# DRV.net
KiCad netlist of a schematic drawn in Altium Designer
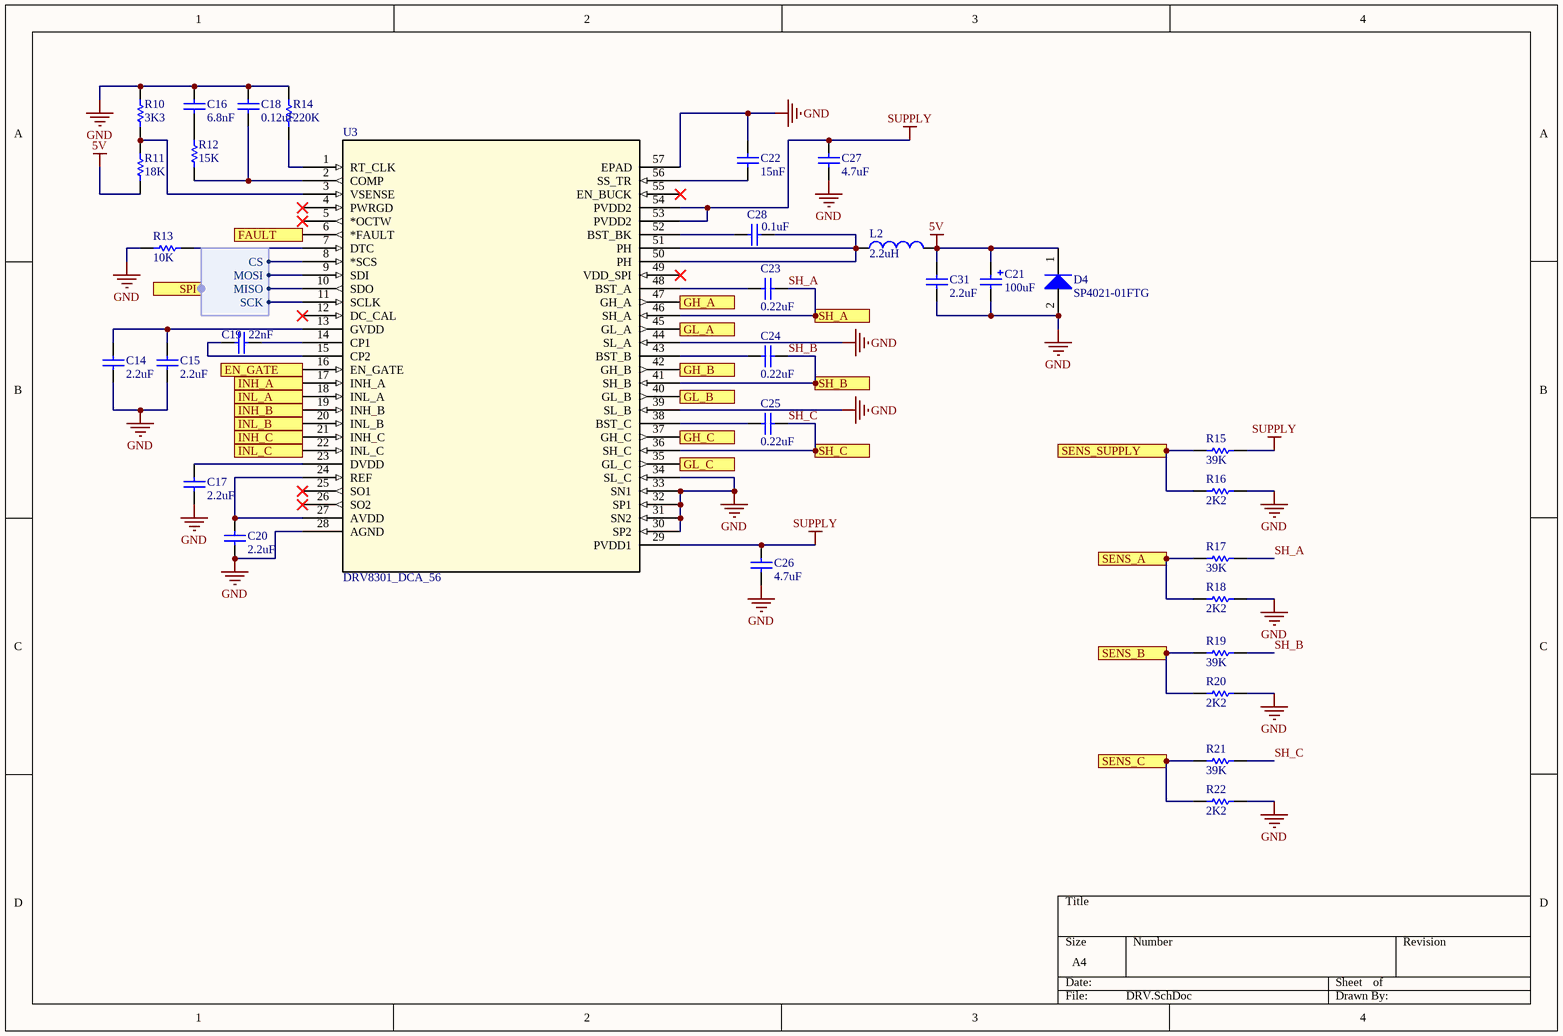
[diagram p0: DRV.SchDoc]

(export (version "E")
  (design (tool "Eeschema 10.0.6"))
  (components
    (comp (ref "C14")
      (value "2.2uF")
      (footprint "C0603[1608X92]")
      (description "2.2uF 25V 10% 0603 (1608 Metric)")
      (fields (field (name "PARTNUMBER") "GRM188R61E225KA12D") (field (name "MANUFACTURER") "Murata"))
      (libsource (lib "Capacitors") (part "CAP_2.2uF_25V_0603_10%"))
    )
    (comp (ref "C15")
      (value "2.2uF")
      (footprint "C0603[1608X92]")
      (description "2.2uF 25V 10% 0603 (1608 Metric)")
      (fields (field (name "PARTNUMBER") "GRM188R61E225KA12D") (field (name "MANUFACTURER") "Murata"))
      (libsource (lib "Capacitors") (part "CAP_2.2uF_25V_0603_10%"))
    )
    (comp (ref "C16")
      (value "6.8nF")
      (footprint "C0603[1608X92]")
      (description "6.8nF 50V 5% 0603 (1608 Metric)")
      (fields (field (name "PARTNUMBER") "GRM1885C1H682JA01D") (field (name "MANUFACTURER") "Murata"))
      (libsource (lib "Capacitors") (part "CAP_6.8nF_50V_0603_5%"))
    )
    (comp (ref "C17")
      (value "2.2uF")
      (footprint "C0603[1608X92]")
      (description "2.2uF 25V 10% 0603 (1608 Metric)")
      (fields (field (name "PARTNUMBER") "GRM188R61E225KA12D") (field (name "MANUFACTURER") "Murata"))
      (libsource (lib "Capacitors") (part "CAP_2.2uF_25V_0603_10%"))
    )
    (comp (ref "C18")
      (value "0.12uF")
      (footprint "C0603[1608X92]")
      (description "0.12uF 10V 10% 0603 (1608 Metric)")
      (fields (field (name "PARTNUMBER") "GRM188R71A124KA01D") (field (name "MANUFACTURER") "Murata"))
      (libsource (lib "Capacitors") (part "CAP_0.12uF_10V_0603_10%"))
    )
    (comp (ref "C19")
      (value "22nF")
      (footprint "C0603[1608X92]")
      (description "22nF 50V 10% 0603 (1608 Metric)")
      (fields (field (name "PARTNUMBER") "GRM188R71H223KA01D") (field (name "MANUFACTURER") "Murata"))
      (libsource (lib "Capacitors") (part "CAP_22nF_50V_0603_10%"))
    )
    (comp (ref "C20")
      (value "2.2uF")
      (footprint "C0603[1608X92]")
      (description "2.2uF 25V 10% 0603 (1608 Metric)")
      (fields (field (name "PARTNUMBER") "GRM188R61E225KA12D") (field (name "MANUFACTURER") "Murata"))
      (libsource (lib "Capacitors") (part "CAP_2.2uF_25V_0603_10%"))
    )
    (comp (ref "C21")
      (value "100uF")
      (footprint "C1206[3216X105]_Tantal")
      (description "TANTAL 100uF 16V 20% 1206 (3216 Metric)")
      (fields (field (name "PARTNUMBER") "F931C107MCCAJ6") (field (name "MANUFACTURER") "AVX Corporation"))
      (libsource (lib "Capacitors") (part "CAP_100uF_16V_1206_20%"))
    )
    (comp (ref "C22")
      (value "15nF")
      (footprint "C0603[1608X92]")
      (description "15nF 50V 5% 0603 (1608 Metric)")
      (fields (field (name "PARTNUMBER") "GRM188R71H153JA01D") (field (name "MANUFACTURER") "Murata"))
      (libsource (lib "Capacitors") (part "CAP_15nF_50V_0603_5%"))
    )
    (comp (ref "C23")
      (value "0.22uF")
      (footprint "C0603[1608X92]")
      (description "0.22uF 50V 10% 0603 (1608 Metric)")
      (fields (field (name "PARTNUMBER") "GRM188R61H224KAC4D") (field (name "MANUFACTURER") "Murata"))
      (libsource (lib "Capacitors") (part "CAP_0.22uF_50V_0603_10%"))
    )
    (comp (ref "C24")
      (value "0.22uF")
      (footprint "C0603[1608X92]")
      (description "0.22uF 50V 10% 0603 (1608 Metric)")
      (fields (field (name "PARTNUMBER") "GRM188R61H224KAC4D") (field (name "MANUFACTURER") "Murata"))
      (libsource (lib "Capacitors") (part "CAP_0.22uF_50V_0603_10%"))
    )
    (comp (ref "C25")
      (value "0.22uF")
      (footprint "C0603[1608X92]")
      (description "0.22uF 50V 10% 0603 (1608 Metric)")
      (fields (field (name "PARTNUMBER") "GRM188R61H224KAC4D") (field (name "MANUFACTURER") "Murata"))
      (libsource (lib "Capacitors") (part "CAP_0.22uF_50V_0603_10%"))
    )
    (comp (ref "C26")
      (value "4.7uF")
      (footprint "C1210[3225X200]")
      (description "4.7uF 100V 10% 1210 (3225 Metric)")
      (fields (field (name "PARTNUMBER") "GRJ32DC72A475KE11L") (field (name "MANUFACTURER") "Murata"))
      (libsource (lib "Capacitors") (part "CAP_4.7uF_100V_1210_10%"))
    )
    (comp (ref "C27")
      (value "4.7uF")
      (footprint "C1210[3225X200]")
      (description "4.7uF 100V 10% 1210 (3225 Metric)")
      (fields (field (name "PARTNUMBER") "GRJ32DC72A475KE11L") (field (name "MANUFACTURER") "Murata"))
      (libsource (lib "Capacitors") (part "CAP_4.7uF_100V_1210_10%"))
    )
    (comp (ref "C28")
      (value "0.1uF")
      (footprint "C0603[1608X92]")
      (description "0.1uF 50V 10% 0603 (1608 Metric)")
      (fields (field (name "PARTNUMBER") "GCM188R71H104KA57D") (field (name "MANUFACTURER") "Murata"))
      (libsource (lib "Capacitors") (part "CAP_0.1uF_50V_0603_10%"))
    )
    (comp (ref "C31")
      (value "2.2uF")
      (footprint "C1206[3216X160]")
      (description "2.2uF 6.3V 10% 1206 (3216 Metric)")
      (fields (field (name "PARTNUMBER") "GRM31CR60J476KE19L") (field (name "MANUFACTURER") "Murata"))
      (libsource (lib "Capacitors") (part "CAP_2.2uF_16V_1206_10%"))
    )
    (comp (ref "D4")
      (value "SP4021-01FTG")
      (footprint "SOD-323")
      (fields (field (name "MANUFACTURER") "Littelfuse"))
      (libsource (lib "Diodes") (part "SP4021-01FTG"))
    )
    (comp (ref "L2")
      (value "2.2uH")
      (footprint "XAL8080")
      (description "2.2uH 38A 4.08mOhms")
      (fields
        (field (name "PARTNUMBER") "XAL8080-270MED")
        (field (name "MANUFACTURER") "Coilcraft")
        (field (name "PUBLISHER") "Altium Limited")
      )
      (libsource (lib "Inductors") (part "XAL8080-220ME_"))
    )
    (comp (ref "R10")
      (value "3K3")
      (footprint "R0603[1608]")
      (description "3K3 0.25W 1% 0603 (1005 Metric)")
      (fields (field (name "MANUFACTURER") "Vishay / Dale") (field (name "PARTNUMBER") "CRCW06033K30FKEAHP"))
      (libsource (lib "Resistors") (part "RES_3K3_0603_1%"))
    )
    (comp (ref "R11")
      (value "18K")
      (footprint "R0603[1608]")
      (description "18K 0.25W 1% 0603 (1005 Metric)")
      (fields (field (name "MANUFACTURER") "Vishay / Dale") (field (name "PARTNUMBER") "CRCW060318K0FKEAHP"))
      (libsource (lib "Resistors") (part "RES_18K_0603_1%"))
    )
    (comp (ref "R12")
      (value "15K")
      (footprint "R0603[1608]")
      (description "15K 0.25W 1% 0603 (1005 Metric)")
      (fields (field (name "MANUFACTURER") "Vishay / Dale") (field (name "PARTNUMBER") "CRCW060315K0FKEAHP"))
      (libsource (lib "Resistors") (part "RES_15K_0603_1%"))
    )
    (comp (ref "R13")
      (value "10K")
      (footprint "R0603[1608]")
      (description "10K 0.25W 1% 0603 (1005 Metric)")
      (fields (field (name "MANUFACTURER") "Vishay") (field (name "PARTNUMBER") "RCS060310K0FKEA"))
      (libsource (lib "Resistors") (part "RES_10K_0603_1%"))
    )
    (comp (ref "R14")
      (value "220K")
      (footprint "R0603[1608]")
      (description "220K 0.25W 1% 0603 (1005 Metric)")
      (fields (field (name "MANUFACTURER") "Vishay / Dale") (field (name "PARTNUMBER") "CRCW0603220KJNEAHP"))
      (libsource (lib "Resistors") (part "RES_220K_0603_1%"))
    )
    (comp (ref "R15")
      (value "39K")
      (footprint "R0603[1608]")
      (description "39K 0.25W 1% 0603 (1005 Metric)")
      (fields (field (name "MANUFACTURER") "Vishay / Dale") (field (name "PARTNUMBER") "CRCW060339K0FKEAHP"))
      (libsource (lib "Resistors") (part "RES_39K_0603_1%"))
    )
    (comp (ref "R16")
      (value "2K2")
      (footprint "R0603[1608]")
      (description "2K2 0.25W 1% 0603 (1005 Metric)")
      (fields (field (name "MANUFACTURER") "Vishay / Dale") (field (name "PARTNUMBER") "CRCW06032K20FKEAHP"))
      (libsource (lib "Resistors") (part "RES_2K2_0603_1%"))
    )
    (comp (ref "R17")
      (value "39K")
      (footprint "R0603[1608]")
      (description "39K 0.25W 1% 0603 (1005 Metric)")
      (fields (field (name "MANUFACTURER") "Vishay / Dale") (field (name "PARTNUMBER") "CRCW060339K0FKEAHP"))
      (libsource (lib "Resistors") (part "RES_39K_0603_1%"))
    )
    (comp (ref "R18")
      (value "2K2")
      (footprint "R0603[1608]")
      (description "2K2 0.25W 1% 0603 (1005 Metric)")
      (fields (field (name "MANUFACTURER") "Vishay / Dale") (field (name "PARTNUMBER") "CRCW06032K20FKEAHP"))
      (libsource (lib "Resistors") (part "RES_2K2_0603_1%"))
    )
    (comp (ref "R19")
      (value "39K")
      (footprint "R0603[1608]")
      (description "39K 0.25W 1% 0603 (1005 Metric)")
      (fields (field (name "MANUFACTURER") "Vishay / Dale") (field (name "PARTNUMBER") "CRCW060339K0FKEAHP"))
      (libsource (lib "Resistors") (part "RES_39K_0603_1%"))
    )
    (comp (ref "R20")
      (value "2K2")
      (footprint "R0603[1608]")
      (description "2K2 0.25W 1% 0603 (1005 Metric)")
      (fields (field (name "MANUFACTURER") "Vishay / Dale") (field (name "PARTNUMBER") "CRCW06032K20FKEAHP"))
      (libsource (lib "Resistors") (part "RES_2K2_0603_1%"))
    )
    (comp (ref "R21")
      (value "39K")
      (footprint "R0603[1608]")
      (description "39K 0.25W 1% 0603 (1005 Metric)")
      (fields (field (name "MANUFACTURER") "Vishay / Dale") (field (name "PARTNUMBER") "CRCW060339K0FKEAHP"))
      (libsource (lib "Resistors") (part "RES_39K_0603_1%"))
    )
    (comp (ref "R22")
      (value "2K2")
      (footprint "R0603[1608]")
      (description "2K2 0.25W 1% 0603 (1005 Metric)")
      (fields (field (name "MANUFACTURER") "Vishay / Dale") (field (name "PARTNUMBER") "CRCW06032K20FKEAHP"))
      (libsource (lib "Resistors") (part "RES_2K2_0603_1%"))
    )
    (comp (ref "U3")
      (value "DRV8301_DCA_56")
      (footprint "DCA56_6P35X3P61")
      (description "Imported")
      (fields
        (field (name "MANUFACTURER") "Texas Instruments")
        (field (name "GENERIC_PART_NUMBER") "DRV8301")
      )
      (libsource (lib "ICs") (part "DRV8301_DCA_56"))
    )
  )
  (nets
    (net (code "2") (name "/CS") (class "Default")
      (node (ref "U3") (pin "8") (pinfunction "*SCS_8") (pintype "input"))
    )
    (net (code "3") (name "/EN_GATE") (class "Default")
      (node (ref "U3") (pin "16") (pinfunction "EN_GATE_16") (pintype "input"))
    )
    (net (code "4") (name "/FAULT") (class "Default")
      (node (ref "U3") (pin "6") (pinfunction "*FAULT_6") (pintype "output"))
    )
    (net (code "5") (name "/GH_A") (class "Default")
      (node (ref "U3") (pin "47") (pinfunction "GH_A_47") (pintype "output"))
    )
    (net (code "6") (name "/GH_B") (class "Default")
      (node (ref "U3") (pin "42") (pinfunction "GH_B_42") (pintype "output"))
    )
    (net (code "7") (name "/GH_C") (class "Default")
      (node (ref "U3") (pin "37") (pinfunction "GH_C_37") (pintype "output"))
    )
    (net (code "8") (name "/GL_A") (class "Default")
      (node (ref "U3") (pin "45") (pinfunction "GL_A_45") (pintype "output"))
    )
    (net (code "9") (name "/GL_B") (class "Default")
      (node (ref "U3") (pin "40") (pinfunction "GL_B_40") (pintype "output"))
    )
    (net (code "10") (name "/GL_C") (class "Default")
      (node (ref "U3") (pin "35") (pinfunction "GL_C_35") (pintype "output"))
    )
    (net (code "11") (name "/INH_A") (class "Default")
      (node (ref "U3") (pin "17") (pinfunction "INH_A_17") (pintype "input"))
    )
    (net (code "12") (name "/INH_B") (class "Default")
      (node (ref "U3") (pin "19") (pinfunction "INH_B_19") (pintype "input"))
    )
    (net (code "13") (name "/INH_C") (class "Default")
      (node (ref "U3") (pin "21") (pinfunction "INH_C_21") (pintype "input"))
    )
    (net (code "14") (name "/INL_A") (class "Default")
      (node (ref "U3") (pin "18") (pinfunction "INL_A_18") (pintype "input"))
    )
    (net (code "15") (name "/INL_B") (class "Default")
      (node (ref "U3") (pin "20") (pinfunction "INL_B_20") (pintype "input"))
    )
    (net (code "16") (name "/INL_C") (class "Default")
      (node (ref "U3") (pin "22") (pinfunction "INL_C_22") (pintype "input"))
    )
    (net (code "17") (name "/MISO") (class "Default")
      (node (ref "U3") (pin "10") (pinfunction "SDO_10") (pintype "output"))
    )
    (net (code "18") (name "/MOSI") (class "Default")
      (node (ref "U3") (pin "9") (pinfunction "SDI_9") (pintype "input"))
    )
    (net (code "19") (name "/SCK") (class "Default")
      (node (ref "U3") (pin "11") (pinfunction "SCLK_11") (pintype "input"))
    )
    (net (code "20") (name "/SENS_A") (class "Default")
      (node (ref "R17") (pin "1") (pinfunction "1_1") (pintype "passive"))
      (node (ref "R18") (pin "1") (pinfunction "1_1") (pintype "passive"))
    )
    (net (code "21") (name "/SENS_B") (class "Default")
      (node (ref "R19") (pin "1") (pinfunction "1_1") (pintype "passive"))
      (node (ref "R20") (pin "1") (pinfunction "1_1") (pintype "passive"))
    )
    (net (code "22") (name "/SENS_C") (class "Default")
      (node (ref "R21") (pin "1") (pinfunction "1_1") (pintype "passive"))
      (node (ref "R22") (pin "1") (pinfunction "1_1") (pintype "passive"))
    )
    (net (code "23") (name "/SENS_SUPPLY") (class "Default")
      (node (ref "R15") (pin "1") (pinfunction "1_1") (pintype "passive"))
      (node (ref "R16") (pin "1") (pinfunction "1_1") (pintype "passive"))
    )
    (net (code "24") (name "/SH_A") (class "Default")
      (node (ref "C23") (pin "2") (pinfunction "2_2") (pintype "passive"))
      (node (ref "R17") (pin "2") (pinfunction "2_2") (pintype "passive"))
      (node (ref "U3") (pin "46") (pinfunction "SH_A_46") (pintype "input"))
    )
    (net (code "25") (name "/SH_B") (class "Default")
      (node (ref "C24") (pin "2") (pinfunction "2_2") (pintype "passive"))
      (node (ref "R19") (pin "2") (pinfunction "2_2") (pintype "passive"))
      (node (ref "U3") (pin "41") (pinfunction "SH_B_41") (pintype "input"))
    )
    (net (code "26") (name "/SH_C") (class "Default")
      (node (ref "C25") (pin "2") (pinfunction "2_2") (pintype "passive"))
      (node (ref "R21") (pin "2") (pinfunction "2_2") (pintype "passive"))
      (node (ref "U3") (pin "36") (pinfunction "SH_C_36") (pintype "input"))
    )
    (net (code "28") (name "5V") (class "Default")
      (node (ref "C21") (pin "1") (pinfunction "1_1") (pintype "passive"))
      (node (ref "C31") (pin "1") (pinfunction "1_1") (pintype "passive"))
      (node (ref "D4") (pin "1") (pinfunction "K_1") (pintype "passive"))
      (node (ref "L2") (pin "2") (pinfunction "2_2") (pintype "passive"))
      (node (ref "R11") (pin "1") (pinfunction "1_1") (pintype "passive"))
    )
    (net (code "29") (name "GND") (class "Default")
      (node (ref "C14") (pin "1") (pinfunction "1_1") (pintype "passive"))
      (node (ref "C15") (pin "1") (pinfunction "1_1") (pintype "passive"))
      (node (ref "C16") (pin "2") (pinfunction "2_2") (pintype "passive"))
      (node (ref "C17") (pin "1") (pinfunction "1_1") (pintype "passive"))
      (node (ref "C18") (pin "2") (pinfunction "2_2") (pintype "passive"))
      (node (ref "C20") (pin "1") (pinfunction "1_1") (pintype "passive"))
      (node (ref "C21") (pin "2") (pinfunction "2_2") (pintype "passive"))
      (node (ref "C22") (pin "2") (pinfunction "2_2") (pintype "passive"))
      (node (ref "C26") (pin "1") (pinfunction "1_1") (pintype "passive"))
      (node (ref "C27") (pin "2") (pinfunction "2_2") (pintype "passive"))
      (node (ref "C31") (pin "2") (pinfunction "2_2") (pintype "passive"))
      (node (ref "D4") (pin "2") (pinfunction "A_2") (pintype "passive"))
      (node (ref "R10") (pin "2") (pinfunction "2_2") (pintype "passive"))
      (node (ref "R13") (pin "1") (pinfunction "1_1") (pintype "passive"))
      (node (ref "R14") (pin "2") (pinfunction "2_2") (pintype "passive"))
      (node (ref "R16") (pin "2") (pinfunction "2_2") (pintype "passive"))
      (node (ref "R18") (pin "2") (pinfunction "2_2") (pintype "passive"))
      (node (ref "R20") (pin "2") (pinfunction "2_2") (pintype "passive"))
      (node (ref "R22") (pin "2") (pinfunction "2_2") (pintype "passive"))
      (node (ref "U3") (pin "28") (pinfunction "AGND_28") (pintype "power_in"))
      (node (ref "U3") (pin "30") (pinfunction "SP2_30") (pintype "input"))
      (node (ref "U3") (pin "31") (pinfunction "SN2_31") (pintype "input"))
      (node (ref "U3") (pin "32") (pinfunction "SP1_32") (pintype "input"))
      (node (ref "U3") (pin "33") (pinfunction "SN1_33") (pintype "input"))
      (node (ref "U3") (pin "34") (pinfunction "SL_C_34") (pintype "input"))
      (node (ref "U3") (pin "39") (pinfunction "SL_B_39") (pintype "input"))
      (node (ref "U3") (pin "44") (pinfunction "SL_A_44") (pintype "input"))
      (node (ref "U3") (pin "57") (pinfunction "EPAD_57") (pintype "passive"))
    )
    (net (code "30") (name "Net-(C16-Pad1)") (class "Default")
      (node (ref "C16") (pin "1") (pinfunction "1_1") (pintype "passive"))
      (node (ref "R12") (pin "2") (pinfunction "2_2") (pintype "passive"))
    )
    (net (code "31") (name "Net-(C28-Pad1)") (class "Default")
      (node (ref "C28") (pin "1") (pinfunction "1_1") (pintype "passive"))
      (node (ref "L2") (pin "1") (pinfunction "1_1") (pintype "passive"))
      (node (ref "U3") (pin "50") (pinfunction "PH_50") (pintype "passive"))
      (node (ref "U3") (pin "51") (pinfunction "PH_51") (pintype "passive"))
    )
    (net (code "32") (name "Net-(U3-AVDD)") (class "Default")
      (node (ref "C20") (pin "2") (pinfunction "2_2") (pintype "passive"))
      (node (ref "U3") (pin "24") (pinfunction "REF_24") (pintype "input"))
      (node (ref "U3") (pin "27") (pinfunction "AVDD_27") (pintype "power_in"))
    )
    (net (code "33") (name "Net-(U3-BST_A)") (class "Default")
      (node (ref "C23") (pin "1") (pinfunction "1_1") (pintype "passive"))
      (node (ref "U3") (pin "48") (pinfunction "BST_A_48") (pintype "power_in"))
    )
    (net (code "34") (name "Net-(U3-BST_B)") (class "Default")
      (node (ref "C24") (pin "1") (pinfunction "1_1") (pintype "passive"))
      (node (ref "U3") (pin "43") (pinfunction "BST_B_43") (pintype "power_in"))
    )
    (net (code "35") (name "Net-(U3-BST_BK)") (class "Default")
      (node (ref "C28") (pin "2") (pinfunction "2_2") (pintype "passive"))
      (node (ref "U3") (pin "52") (pinfunction "BST_BK_52") (pintype "power_in"))
    )
    (net (code "36") (name "Net-(U3-BST_C)") (class "Default")
      (node (ref "C25") (pin "1") (pinfunction "1_1") (pintype "passive"))
      (node (ref "U3") (pin "38") (pinfunction "BST_C_38") (pintype "power_in"))
    )
    (net (code "37") (name "Net-(U3-COMP)") (class "Default")
      (node (ref "C18") (pin "1") (pinfunction "1_1") (pintype "passive"))
      (node (ref "R12") (pin "1") (pinfunction "1_1") (pintype "passive"))
      (node (ref "U3") (pin "2") (pinfunction "COMP_2") (pintype "output"))
    )
    (net (code "38") (name "Net-(U3-CP1)") (class "Default")
      (node (ref "C19") (pin "1") (pinfunction "1_1") (pintype "passive"))
      (node (ref "U3") (pin "14") (pinfunction "CP1_14") (pintype "power_in"))
    )
    (net (code "39") (name "Net-(U3-CP2)") (class "Default")
      (node (ref "C19") (pin "2") (pinfunction "2_2") (pintype "passive"))
      (node (ref "U3") (pin "15") (pinfunction "CP2_15") (pintype "power_in"))
    )
    (net (code "40") (name "Net-(U3-DTC)") (class "Default")
      (node (ref "R13") (pin "2") (pinfunction "2_2") (pintype "passive"))
      (node (ref "U3") (pin "7") (pinfunction "DTC_7") (pintype "input"))
    )
    (net (code "41") (name "Net-(U3-DVDD)") (class "Default")
      (node (ref "C17") (pin "2") (pinfunction "2_2") (pintype "passive"))
      (node (ref "U3") (pin "23") (pinfunction "DVDD_23") (pintype "power_in"))
    )
    (net (code "42") (name "Net-(U3-GVDD)") (class "Default")
      (node (ref "C14") (pin "2") (pinfunction "2_2") (pintype "passive"))
      (node (ref "C15") (pin "2") (pinfunction "2_2") (pintype "passive"))
      (node (ref "U3") (pin "13") (pinfunction "GVDD_13") (pintype "power_in"))
    )
    (net (code "43") (name "Net-(U3-RT_CLK)") (class "Default")
      (node (ref "R14") (pin "1") (pinfunction "1_1") (pintype "passive"))
      (node (ref "U3") (pin "1") (pinfunction "RT_CLK_1") (pintype "input"))
    )
    (net (code "44") (name "Net-(U3-SS_TR)") (class "Default")
      (node (ref "C22") (pin "1") (pinfunction "1_1") (pintype "passive"))
      (node (ref "U3") (pin "56") (pinfunction "SS_TR_56") (pintype "input"))
    )
    (net (code "45") (name "Net-(U3-VSENSE)") (class "Default")
      (node (ref "R10") (pin "1") (pinfunction "1_1") (pintype "passive"))
      (node (ref "R11") (pin "2") (pinfunction "2_2") (pintype "passive"))
      (node (ref "U3") (pin "3") (pinfunction "VSENSE_3") (pintype "input"))
    )
    (net (code "46") (name "SUPPLY") (class "Default")
      (node (ref "C26") (pin "2") (pinfunction "2_2") (pintype "passive"))
      (node (ref "C27") (pin "1") (pinfunction "1_1") (pintype "passive"))
      (node (ref "R15") (pin "2") (pinfunction "2_2") (pintype "passive"))
      (node (ref "U3") (pin "29") (pinfunction "PVDD1_29") (pintype "power_in"))
      (node (ref "U3") (pin "53") (pinfunction "PVDD2_53") (pintype "power_in"))
      (node (ref "U3") (pin "54") (pinfunction "PVDD2_54") (pintype "power_in"))
    )
    (net (code "47") (name "unconnected-(U3-*OCTW-Pad5)") (class "Default")
      (node (ref "U3") (pin "5") (pinfunction "*OCTW_5") (pintype "output+no_connect"))
    )
    (net (code "48") (name "unconnected-(U3-DC_CAL-Pad12)") (class "Default")
      (node (ref "U3") (pin "12") (pinfunction "DC_CAL_12") (pintype "input+no_connect"))
    )
    (net (code "49") (name "unconnected-(U3-EN_BUCK-Pad55)") (class "Default")
      (node (ref "U3") (pin "55") (pinfunction "EN_BUCK_55") (pintype "input+no_connect"))
    )
    (net (code "50") (name "unconnected-(U3-PWRGD-Pad4)") (class "Default")
      (node (ref "U3") (pin "4") (pinfunction "PWRGD_4") (pintype "input+no_connect"))
    )
    (net (code "51") (name "unconnected-(U3-SO1-Pad25)") (class "Default")
      (node (ref "U3") (pin "25") (pinfunction "SO1_25") (pintype "output+no_connect"))
    )
    (net (code "52") (name "unconnected-(U3-SO2-Pad26)") (class "Default")
      (node (ref "U3") (pin "26") (pinfunction "SO2_26") (pintype "output+no_connect"))
    )
    (net (code "53") (name "unconnected-(U3-VDD_SPI-Pad49)") (class "Default")
      (node (ref "U3") (pin "49") (pinfunction "VDD_SPI_49") (pintype "input+no_connect"))
    )
  )
)
